# Sheet1-backup.net
KiCad netlist of a schematic drawn in Altium Designer
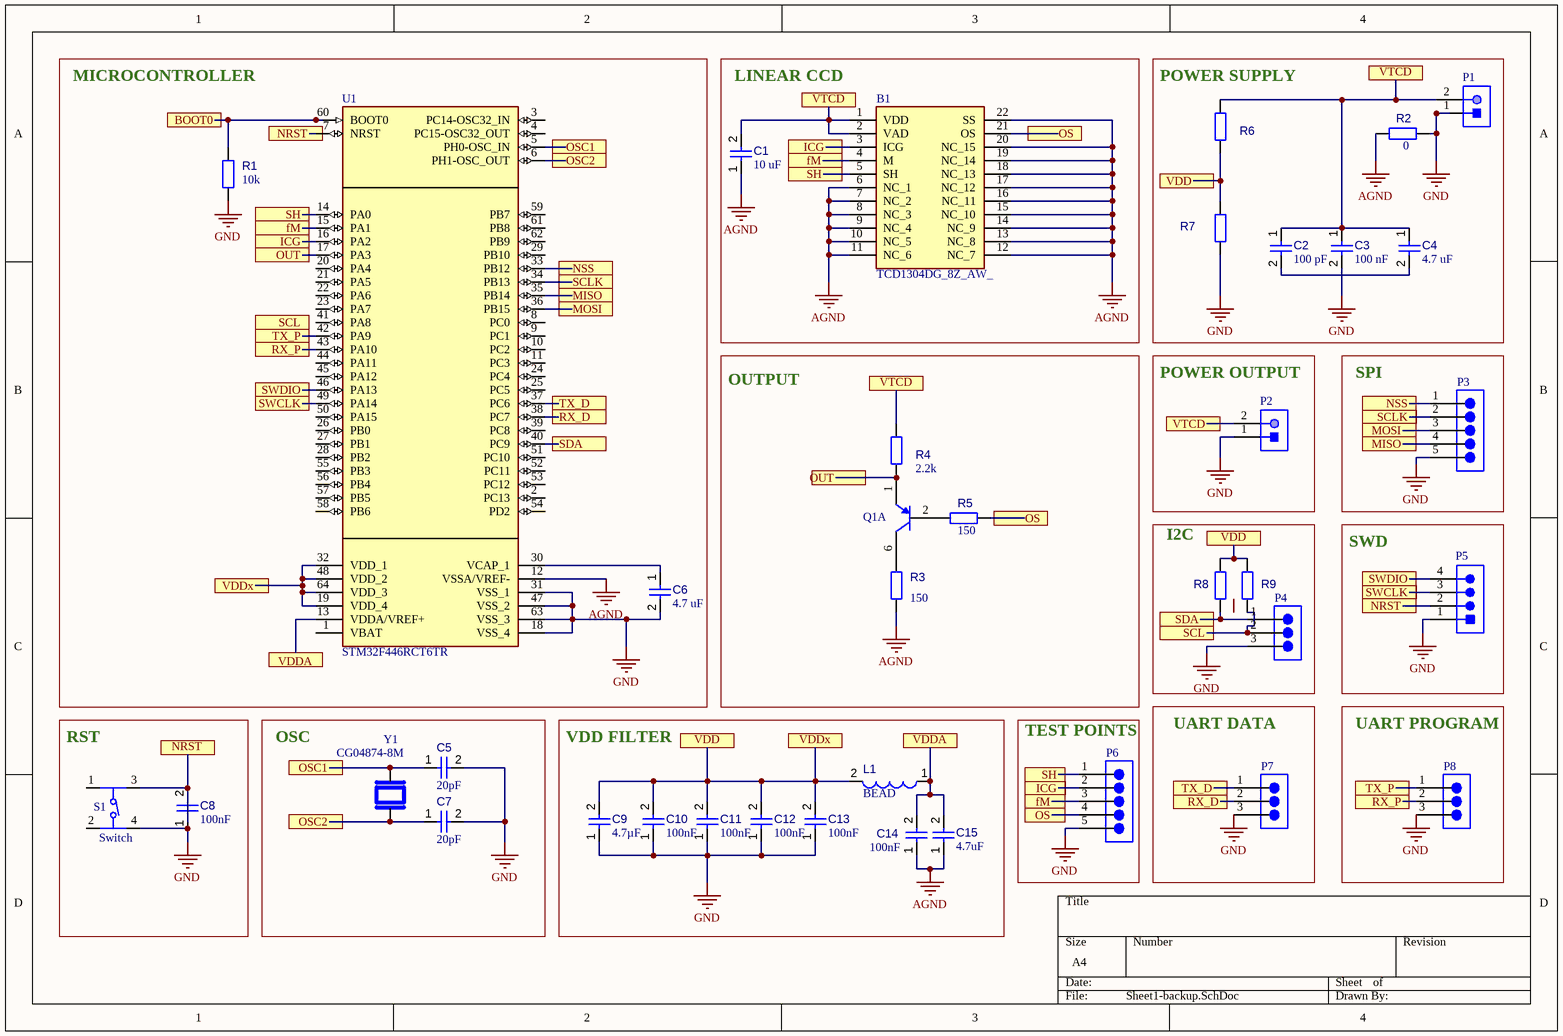
[diagram p0: Sheet1-backup.SchDoc]

(export (version "E")
  (design (tool "Eeschema 10.0.6"))
  (components
    (comp (ref "B1")
      (value "TCD1304DG_8Z_AW_")
      (footprint "DIP1016W62P254L4160H372Q22N")
      (description "Image Sensors & Color Sensors CCD Linear Sensor 3648 8x20 54mm")
      (fields
        (field (name "MOUSER PART NUMBER") "757-TCD1304DG8ZAW")
        (field (name "MANUFACTURER_PART_NUMBER") "TCD1304DG(8Z,AW)")
      )
      (libsource (lib "Sensors") (part "TCD1304DG_8Z_AW_"))
    )
    (comp (ref "C1")
      (value "10 uF")
      (footprint "CAPC1005X56X25LL10T15")
      (description "Chip Capacitor, 0.1 uF, +/- 5%, 16 V, 0402 (1005 Metric)")
      (fields (field (name "TOLERANCE") "5%") (field (name "Comment") "Capacitor 0.1 uF +/- 5% 16 V 0402"))
      (libsource (lib "Francisco Spaltro") (part "CAP-NP-2"))
    )
    (comp (ref "C2")
      (value "100 pF")
      (footprint "CAPC2013X95X50LL10T25")
      (description "Chip Capacitor, 100 nF, +/- 10%, 50 V, 0805 (2012 Metric)")
      (fields (field (name "TOLERANCE") "10%") (field (name "Comment") "Capacitor 100 nF +/-10% 50 V 0805"))
      (libsource (lib "Francisco Spaltro") (part "CAP-NP-2"))
    )
    (comp (ref "C3")
      (value "100 nF")
      (footprint "CAPC2013X95X50LL10T25")
      (description "Chip Capacitor, 100 nF, +/- 10%, 50 V, 0805 (2012 Metric)")
      (fields (field (name "TOLERANCE") "10%") (field (name "Comment") "Capacitor 100 nF +/-10% 50 V 0805"))
      (libsource (lib "Francisco Spaltro") (part "CAP-NP-2"))
    )
    (comp (ref "C4")
      (value "4.7 uF")
      (footprint "CAPC2013X95X50LL10T25")
      (description "Chip Capacitor, 100 nF, +/- 10%, 50 V, 0805 (2012 Metric)")
      (fields (field (name "TOLERANCE") "10%") (field (name "Comment") "Capacitor 100 nF +/-10% 50 V 0805"))
      (libsource (lib "Francisco Spaltro") (part "CAP-NP-2"))
    )
    (comp (ref "C5")
      (value "20pF")
      (footprint "CAPC1005X56X25ML10T15")
      (description "Chip Capacitor, 0.5 pF, +/- 0.1pF, 25 V, 0402 (1005 Metric)")
      (fields
        (field (name "TOLERANCE") "20%")
        (field (name "Comment") "Capacitor 0.5 pF +/- 0.1pF 25 V 0402")
      )
      (libsource (lib "Francisco Spaltro") (part "CAP-NP-2"))
    )
    (comp (ref "C6")
      (value "4.7 uF")
      (footprint "CAPC2013X95X50LL10T25")
      (description "Chip Capacitor, 100 nF, +/- 10%, 50 V, 0805 (2012 Metric)")
      (fields (field (name "TOLERANCE") "10%") (field (name "Comment") "Capacitor 100 nF +/-10% 50 V 0805"))
      (libsource (lib "Francisco Spaltro") (part "CAP-NP-2"))
    )
    (comp (ref "C7")
      (value "20pF")
      (footprint "CAPC1005X56X25ML10T15")
      (description "Chip Capacitor, 0.5 pF, +/- 0.1pF, 25 V, 0402 (1005 Metric)")
      (fields
        (field (name "TOLERANCE") "20%")
        (field (name "Comment") "Capacitor 0.5 pF +/- 0.1pF 25 V 0402")
      )
      (libsource (lib "Francisco Spaltro") (part "CAP-NP-2"))
    )
    (comp (ref "C8")
      (value "100nF")
      (footprint "CAPC1005X56X25LL10T15")
      (description "Chip Capacitor, 0.1 uF, +/- 5%, 16 V, 0402 (1005 Metric)")
      (fields (field (name "TOLERANCE") "5%") (field (name "Comment") "Capacitor 0.1 uF +/- 5% 16 V 0402"))
      (libsource (lib "Francisco Spaltro") (part "CAP-NP-2"))
    )
    (comp (ref "C9")
      (value "4.7µF")
      (footprint "CAPC0603(1608)100_L")
      (description "Chip Capacitor, 4.7µF +/-20%, 10V, 0603, Thickness 1 mm")
      (fields (field (name "TOLERANCE") "10%") (field (name "Comment") "Capacitor 4.7µF +/-20% 10V 0603"))
      (libsource (lib "Francisco Spaltro") (part "CAP-NP-2"))
    )
    (comp (ref "C10")
      (value "100nF")
      (footprint "CAPC2013X95X50LL10T25")
      (description "Chip Capacitor, 100 nF, +/- 10%, 50 V, 0805 (2012 Metric)")
      (fields (field (name "TOLERANCE") "10%") (field (name "Comment") "Capacitor 100 nF +/-10% 50 V 0805"))
      (libsource (lib "Francisco Spaltro") (part "CAP-NP-2"))
    )
    (comp (ref "C11")
      (value "100nF")
      (footprint "CAPC2013X95X50LL10T25")
      (description "Chip Capacitor, 100 nF, +/- 10%, 50 V, 0805 (2012 Metric)")
      (fields (field (name "TOLERANCE") "10%") (field (name "Comment") "Capacitor 100 nF +/-10% 50 V 0805"))
      (libsource (lib "Francisco Spaltro") (part "CAP-NP-2"))
    )
    (comp (ref "C12")
      (value "100nF")
      (footprint "CAPC2013X95X50LL10T25")
      (description "Chip Capacitor, 100 nF, +/- 10%, 50 V, 0805 (2012 Metric)")
      (fields (field (name "TOLERANCE") "10%") (field (name "Comment") "Capacitor 100 nF +/-10% 50 V 0805"))
      (libsource (lib "Francisco Spaltro") (part "CAP-NP-2"))
    )
    (comp (ref "C13")
      (value "100nF")
      (footprint "CAPC2013X95X50LL10T25")
      (description "Chip Capacitor, 100 nF, +/- 10%, 50 V, 0805 (2012 Metric)")
      (fields (field (name "TOLERANCE") "10%") (field (name "Comment") "Capacitor 100 nF +/-10% 50 V 0805"))
      (libsource (lib "Francisco Spaltro") (part "CAP-NP-2"))
    )
    (comp (ref "C14")
      (value "100nF")
      (footprint "CAPC2013X95X50LL10T25")
      (description "Chip Capacitor, 100 nF, +/- 10%, 50 V, 0805 (2012 Metric)")
      (fields (field (name "TOLERANCE") "10%") (field (name "Comment") "Capacitor 100 nF +/-10% 50 V 0805"))
      (libsource (lib "Francisco Spaltro") (part "CAP-NP-2"))
    )
    (comp (ref "C15")
      (value "4.7uF")
      (footprint "CAPC2013X95X50LL10T25")
      (description "Chip Capacitor, 100 nF, +/- 10%, 50 V, 0805 (2012 Metric)")
      (fields (field (name "TOLERANCE") "10%") (field (name "Comment") "Capacitor 100 nF +/-10% 50 V 0805"))
      (libsource (lib "Francisco Spaltro") (part "CAP-NP-2"))
    )
    (comp (ref "L1")
      (value "BEAD")
      (footprint "WE-LQS 4018")
      (description "WE-LQS SMD Power Inductor, L=33 µH")
      (fields (field (name "TOLERANCE") "20%") (field (name "Comment") "74404042330"))
      (libsource (lib "Francisco Spaltro") (part "CMP-001-0020-1"))
    )
    (comp (ref "P1")
      (value "~")
      (footprint "JST-S2B-PH-K-S_V")
      (fields (field (name "MANUFACTURER") "Japan Solderless Terminals"))
      (libsource (lib "Francisco Spaltro") (part "CN-1P-M-R2"))
    )
    (comp (ref "P2")
      (value "~")
      (footprint "JST-S2B-PH-K-S_V")
      (fields (field (name "MANUFACTURER") "Japan Solderless Terminals"))
      (libsource (lib "Francisco Spaltro") (part "CN-1P-M-R2"))
    )
    (comp (ref "P3")
      (value "~")
      (footprint "PCB_5POS_PIN")
      (libsource (lib "Componentes") (part "5-POS-PIN"))
    )
    (comp (ref "P4")
      (value "~")
      (footprint "PCB_3POS_PIN")
      (libsource (lib "Componentes") (part "3-POS-PIN"))
    )
    (comp (ref "P5")
      (value "~")
      (footprint "JST-S4B-XH-A(LF)(SN)_V")
      (fields (field (name "MANUFACTURER") "JST"))
      (libsource (lib "Francisco Spaltro") (part "CN-1P-M-R4"))
    )
    (comp (ref "P6")
      (value "~")
      (footprint "PCB_5POS_PIN")
      (libsource (lib "Componentes") (part "5-POS-PIN"))
    )
    (comp (ref "P7")
      (value "~")
      (footprint "PCB_3POS_PIN")
      (libsource (lib "Componentes") (part "3-POS-PIN"))
    )
    (comp (ref "P8")
      (value "~")
      (footprint "PCB_3POS_PIN")
      (libsource (lib "Componentes") (part "3-POS-PIN"))
    )
    (comp (ref "Q1")
      (value "~")
      (footprint "NXP-SOT457-6_V")
      (description "PNP/PNP Matched Double Transistors, 175 MHz, -65 to 150 degC, 6-Pin SOT457, RoHS, Tape and Reel")
      (fields (field (name "MANUFACTURER") "NXP") (field (name "POWER") "380mW"))
      (libsource (lib "Francisco Spaltro") (part "BJT-PNP-EBC-EBC-6"))
    )
    (comp (ref "R1")
      (value "10k")
      (footprint "RESC0402(1005)_L")
      (description "10K 0.063W 1% 0402 (1005 Metric)  SMD")
      (fields (field (name "POWER") "63mW") (field (name "TOLERANCE") "1%"))
      (libsource (lib "") (part "10KR2F_1"))
    )
    (comp (ref "R2")
      (value "0")
      (footprint "RESC0402(1005)_L")
      (description "10K 0.063W 1% 0402 (1005 Metric)  SMD")
      (fields (field (name "POWER") "63mW") (field (name "TOLERANCE") "1%"))
      (libsource (lib "Francisco Spaltro") (part "10KR2F"))
    )
    (comp (ref "R3")
      (value "150")
      (footprint "RESC0402(1005)_L")
      (description "10K 0.063W 1% 0402 (1005 Metric)  SMD")
      (fields (field (name "POWER") "63mW") (field (name "TOLERANCE") "1%"))
      (libsource (lib "") (part "10KR2F_2"))
    )
    (comp (ref "R4")
      (value "2.2k")
      (footprint "RESC0402(1005)_L")
      (description "10K 0.063W 1% 0402 (1005 Metric)  SMD")
      (fields (field (name "POWER") "63mW") (field (name "TOLERANCE") "1%"))
      (libsource (lib "") (part "10KR2F_2"))
    )
    (comp (ref "R5")
      (value "150")
      (footprint "RESC0402(1005)_L")
      (description "10K 0.063W 1% 0402 (1005 Metric)  SMD")
      (fields (field (name "POWER") "63mW") (field (name "TOLERANCE") "1%"))
      (libsource (lib "Francisco Spaltro") (part "10KR2F"))
    )
    (comp (ref "R6")
      (value "10KR2F")
      (footprint "RESC0402(1005)_L")
      (description "10K 0.063W 1% 0402 (1005 Metric)  SMD")
      (fields (field (name "POWER") "63mW") (field (name "TOLERANCE") "1%"))
      (libsource (lib "") (part "10KR2F_2"))
    )
    (comp (ref "R7")
      (value "10KR2F")
      (footprint "RESC0402(1005)_L")
      (description "10K 0.063W 1% 0402 (1005 Metric)  SMD")
      (fields (field (name "POWER") "63mW") (field (name "TOLERANCE") "1%"))
      (libsource (lib "") (part "10KR2F_2"))
    )
    (comp (ref "R8")
      (value "10KR2F")
      (footprint "RESC0402(1005)_L")
      (description "10K 0.063W 1% 0402 (1005 Metric)  SMD")
      (fields (field (name "POWER") "63mW") (field (name "TOLERANCE") "1%"))
      (libsource (lib "") (part "10KR2F_2"))
    )
    (comp (ref "R9")
      (value "10KR2F")
      (footprint "RESC0402(1005)_L")
      (description "10K 0.063W 1% 0402 (1005 Metric)  SMD")
      (fields (field (name "POWER") "63mW") (field (name "TOLERANCE") "1%"))
      (libsource (lib "") (part "10KR2F_2"))
    )
    (comp (ref "S1")
      (value "Switch")
      (footprint "430152070826")
      (description "Tactile Switch SPST-NO Top Actuated Surface Mount")
      (fields (field (name "MF") "WÃ¼rth Elektronik") (field (name "MP") "430152070826"))
      (libsource (lib "Componentes") (part "Switch"))
    )
    (comp (ref "U1")
      (value "STM32F446RCT6TR")
      (footprint "QFP50P1200X1200X160-64N")
      (fields (field (name "MF") "STMicroelectronics"))
      (libsource (lib "IC") (part "STM32F446RCT6TR"))
    )
    (comp (ref "Y1")
      (value "CG04874-8M")
      (footprint "XTALDFN320X250X100-2N")
      (description "8 MHz ±20ppm Crystal 8pF 500 Ohms 2-SMD, No Lead")
      (fields (field (name "MF") "NDK America, Inc."))
      (libsource (lib "Componentes") (part "CG04874-8M"))
    )
  )
  (nets
    (net (code "1") (name "/BOOT0") (class "Default")
      (node (ref "R1") (pin "2") (pinfunction "2_2") (pintype "passive"))
      (node (ref "U1") (pin "60") (pinfunction "BOOT0_60") (pintype "input"))
    )
    (net (code "2") (name "/ICG") (class "Default")
      (node (ref "B1") (pin "3") (pinfunction "ICG_3") (pintype "passive"))
      (node (ref "P6") (pin "2") (pinfunction "2_2") (pintype "passive"))
      (node (ref "U1") (pin "16") (pinfunction "PA2_16") (pintype "bidirectional"))
    )
    (net (code "3") (name "/MISO") (class "Default")
      (node (ref "P3") (pin "4") (pinfunction "4_4") (pintype "passive"))
      (node (ref "U1") (pin "35") (pinfunction "PB14_35") (pintype "bidirectional"))
    )
    (net (code "4") (name "/MOSI") (class "Default")
      (node (ref "P3") (pin "3") (pinfunction "3_3") (pintype "passive"))
      (node (ref "U1") (pin "36") (pinfunction "PB15_36") (pintype "bidirectional"))
    )
    (net (code "5") (name "/NRST") (class "Default")
      (node (ref "C8") (pin "2") (pinfunction "2_2") (pintype "passive"))
      (node (ref "P5") (pin "2") (pinfunction "2_2") (pintype "passive"))
      (node (ref "S1") (pin "3") (pinfunction "3_3") (pintype "passive"))
      (node (ref "U1") (pin "7") (pinfunction "NRST_7") (pintype "bidirectional"))
    )
    (net (code "6") (name "/NSS") (class "Default")
      (node (ref "P3") (pin "1") (pinfunction "1_1") (pintype "passive"))
      (node (ref "U1") (pin "33") (pinfunction "PB12_33") (pintype "bidirectional"))
    )
    (net (code "7") (name "/OS") (class "Default")
      (node (ref "B1") (pin "21") (pinfunction "OS_21") (pintype "passive"))
      (node (ref "P6") (pin "4") (pinfunction "4_4") (pintype "passive"))
      (node (ref "R5") (pin "1") (pinfunction "1_1") (pintype "passive"))
    )
    (net (code "8") (name "/OSC1") (class "Default")
      (node (ref "C5") (pin "1") (pinfunction "1_1") (pintype "passive"))
      (node (ref "U1") (pin "5") (pinfunction "PH0-OSC_IN_5") (pintype "bidirectional"))
      (node (ref "Y1") (pin "2") (pinfunction "2_2") (pintype "passive"))
    )
    (net (code "9") (name "/OSC2") (class "Default")
      (node (ref "C7") (pin "1") (pinfunction "1_1") (pintype "passive"))
      (node (ref "U1") (pin "6") (pinfunction "PH1-OSC_OUT_6") (pintype "bidirectional"))
      (node (ref "Y1") (pin "1") (pinfunction "1_1") (pintype "passive"))
    )
    (net (code "10") (name "/OUT") (class "Default")
      (node (ref "Q1") (pin "1") (pinfunction "E1_1") (pintype "passive"))
      (node (ref "R4") (pin "2") (pinfunction "2_2") (pintype "passive"))
      (node (ref "U1") (pin "17") (pinfunction "PA3_17") (pintype "bidirectional"))
    )
    (net (code "11") (name "/RX_D") (class "Default")
      (node (ref "P7") (pin "2") (pinfunction "2_2") (pintype "passive"))
      (node (ref "U1") (pin "38") (pinfunction "PC7_38") (pintype "bidirectional"))
    )
    (net (code "12") (name "/RX_P") (class "Default")
      (node (ref "P8") (pin "2") (pinfunction "2_2") (pintype "passive"))
      (node (ref "U1") (pin "43") (pinfunction "PA10_43") (pintype "bidirectional"))
    )
    (net (code "13") (name "/SCL") (class "Default")
      (node (ref "P4") (pin "2") (pinfunction "2_2") (pintype "passive"))
      (node (ref "R9") (pin "2") (pinfunction "2_2") (pintype "passive"))
    )
    (net (code "14") (name "/SCLK") (class "Default")
      (node (ref "P3") (pin "2") (pinfunction "2_2") (pintype "passive"))
      (node (ref "U1") (pin "34") (pinfunction "PB13_34") (pintype "bidirectional"))
    )
    (net (code "15") (name "/SDA") (class "Default")
      (node (ref "P4") (pin "1") (pinfunction "1_1") (pintype "passive"))
      (node (ref "R8") (pin "2") (pinfunction "2_2") (pintype "passive"))
      (node (ref "U1") (pin "40") (pinfunction "PC9_40") (pintype "bidirectional"))
    )
    (net (code "16") (name "/SH") (class "Default")
      (node (ref "B1") (pin "5") (pinfunction "SH_5") (pintype "passive"))
      (node (ref "P6") (pin "1") (pinfunction "1_1") (pintype "passive"))
      (node (ref "U1") (pin "14") (pinfunction "PA0_14") (pintype "bidirectional"))
    )
    (net (code "17") (name "/SWCLK") (class "Default")
      (node (ref "P5") (pin "3") (pinfunction "3_3") (pintype "passive"))
      (node (ref "U1") (pin "49") (pinfunction "PA14_49") (pintype "bidirectional"))
    )
    (net (code "18") (name "/SWDIO") (class "Default")
      (node (ref "P5") (pin "4") (pinfunction "4_4") (pintype "passive"))
      (node (ref "U1") (pin "46") (pinfunction "PA13_46") (pintype "bidirectional"))
    )
    (net (code "19") (name "/TX_D") (class "Default")
      (node (ref "P7") (pin "1") (pinfunction "1_1") (pintype "passive"))
      (node (ref "U1") (pin "37") (pinfunction "PC6_37") (pintype "bidirectional"))
    )
    (net (code "20") (name "/TX_P") (class "Default")
      (node (ref "P8") (pin "1") (pinfunction "1_1") (pintype "passive"))
      (node (ref "U1") (pin "42") (pinfunction "PA9_42") (pintype "bidirectional"))
    )
    (net (code "21") (name "/VDD") (class "Default")
      (node (ref "C10") (pin "2") (pinfunction "2_2") (pintype "passive"))
      (node (ref "C11") (pin "2") (pinfunction "2_2") (pintype "passive"))
      (node (ref "C12") (pin "2") (pinfunction "2_2") (pintype "passive"))
      (node (ref "C13") (pin "2") (pinfunction "2_2") (pintype "passive"))
      (node (ref "C9") (pin "2") (pinfunction "2_2") (pintype "passive"))
      (node (ref "L1") (pin "2") (pinfunction "2_2") (pintype "passive"))
      (node (ref "R6") (pin "2") (pinfunction "2_2") (pintype "passive"))
      (node (ref "R7") (pin "1") (pinfunction "1_1") (pintype "passive"))
      (node (ref "R8") (pin "1") (pinfunction "1_1") (pintype "passive"))
      (node (ref "R9") (pin "1") (pinfunction "1_1") (pintype "passive"))
      (node (ref "U1") (pin "19") (pinfunction "VDD_4_19") (pintype "power_in"))
      (node (ref "U1") (pin "32") (pinfunction "VDD_1_32") (pintype "power_in"))
      (node (ref "U1") (pin "48") (pinfunction "VDD_2_48") (pintype "power_in"))
      (node (ref "U1") (pin "64") (pinfunction "VDD_3_64") (pintype "power_in"))
    )
    (net (code "22") (name "/VDDA") (class "Default")
      (node (ref "C14") (pin "2") (pinfunction "2_2") (pintype "passive"))
      (node (ref "C15") (pin "2") (pinfunction "2_2") (pintype "passive"))
      (node (ref "L1") (pin "1") (pinfunction "1_1") (pintype "passive"))
      (node (ref "U1") (pin "13") (pinfunction "VDDA/VREF+_13") (pintype "power_in"))
    )
    (net (code "23") (name "/VTCD") (class "Default")
      (node (ref "B1") (pin "1") (pinfunction "VDD_1") (pintype "power_in"))
      (node (ref "B1") (pin "2") (pinfunction "VAD_2") (pintype "power_in"))
      (node (ref "C1") (pin "2") (pinfunction "2_2") (pintype "passive"))
      (node (ref "C2") (pin "1") (pinfunction "1_1") (pintype "passive"))
      (node (ref "C3") (pin "1") (pinfunction "1_1") (pintype "passive"))
      (node (ref "C4") (pin "1") (pinfunction "1_1") (pintype "passive"))
      (node (ref "P1") (pin "2") (pinfunction "2_2") (pintype "passive"))
      (node (ref "P2") (pin "2") (pinfunction "2_2") (pintype "passive"))
      (node (ref "R4") (pin "1") (pinfunction "1_1") (pintype "passive"))
      (node (ref "R6") (pin "1") (pinfunction "1_1") (pintype "passive"))
    )
    (net (code "24") (name "/fM") (class "Default")
      (node (ref "B1") (pin "4") (pinfunction "M_4") (pintype "passive"))
      (node (ref "P6") (pin "3") (pinfunction "3_3") (pintype "passive"))
      (node (ref "U1") (pin "15") (pinfunction "PA1_15") (pintype "bidirectional"))
    )
    (net (code "25") (name "AGND") (class "Default")
      (node (ref "B1") (pin "10") (pinfunction "NC_5_10") (pintype "passive"))
      (node (ref "B1") (pin "11") (pinfunction "NC_6_11") (pintype "passive"))
      (node (ref "B1") (pin "12") (pinfunction "NC_7_12") (pintype "passive"))
      (node (ref "B1") (pin "13") (pinfunction "NC_8_13") (pintype "passive"))
      (node (ref "B1") (pin "14") (pinfunction "NC_9_14") (pintype "passive"))
      (node (ref "B1") (pin "15") (pinfunction "NC_10_15") (pintype "passive"))
      (node (ref "B1") (pin "16") (pinfunction "NC_11_16") (pintype "passive"))
      (node (ref "B1") (pin "17") (pinfunction "NC_12_17") (pintype "passive"))
      (node (ref "B1") (pin "18") (pinfunction "NC_13_18") (pintype "passive"))
      (node (ref "B1") (pin "19") (pinfunction "NC_14_19") (pintype "passive"))
      (node (ref "B1") (pin "20") (pinfunction "NC_15_20") (pintype "passive"))
      (node (ref "B1") (pin "22") (pinfunction "SS_22") (pintype "passive"))
      (node (ref "B1") (pin "6") (pinfunction "NC_1_6") (pintype "passive"))
      (node (ref "B1") (pin "7") (pinfunction "NC_2_7") (pintype "passive"))
      (node (ref "B1") (pin "8") (pinfunction "NC_3_8") (pintype "passive"))
      (node (ref "B1") (pin "9") (pinfunction "NC_4_9") (pintype "passive"))
      (node (ref "C1") (pin "1") (pinfunction "1_1") (pintype "passive"))
      (node (ref "C14") (pin "1") (pinfunction "1_1") (pintype "passive"))
      (node (ref "C15") (pin "1") (pinfunction "1_1") (pintype "passive"))
      (node (ref "R2") (pin "2") (pinfunction "2_2") (pintype "passive"))
      (node (ref "R3") (pin "2") (pinfunction "2_2") (pintype "passive"))
      (node (ref "U1") (pin "12") (pinfunction "VSSA/VREF-_12") (pintype "power_in"))
    )
    (net (code "26") (name "GND") (class "Default")
      (node (ref "C10") (pin "1") (pinfunction "1_1") (pintype "passive"))
      (node (ref "C11") (pin "1") (pinfunction "1_1") (pintype "passive"))
      (node (ref "C12") (pin "1") (pinfunction "1_1") (pintype "passive"))
      (node (ref "C13") (pin "1") (pinfunction "1_1") (pintype "passive"))
      (node (ref "C3") (pin "2") (pinfunction "2_2") (pintype "passive"))
      (node (ref "C5") (pin "2") (pinfunction "2_2") (pintype "passive"))
      (node (ref "C6") (pin "2") (pinfunction "2_2") (pintype "passive"))
      (node (ref "C7") (pin "2") (pinfunction "2_2") (pintype "passive"))
      (node (ref "C8") (pin "1") (pinfunction "1_1") (pintype "passive"))
      (node (ref "C9") (pin "1") (pinfunction "1_1") (pintype "passive"))
      (node (ref "P1") (pin "1") (pinfunction "1_1") (pintype "passive"))
      (node (ref "P2") (pin "1") (pinfunction "1_1") (pintype "passive"))
      (node (ref "P3") (pin "5") (pinfunction "5_5") (pintype "passive"))
      (node (ref "P4") (pin "3") (pinfunction "3_3") (pintype "passive"))
      (node (ref "P5") (pin "1") (pinfunction "1_1") (pintype "passive"))
      (node (ref "P6") (pin "5") (pinfunction "5_5") (pintype "passive"))
      (node (ref "P7") (pin "3") (pinfunction "3_3") (pintype "passive"))
      (node (ref "P8") (pin "3") (pinfunction "3_3") (pintype "passive"))
      (node (ref "R1") (pin "1") (pinfunction "1_1") (pintype "passive"))
      (node (ref "R2") (pin "1") (pinfunction "1_1") (pintype "passive"))
      (node (ref "R7") (pin "2") (pinfunction "2_2") (pintype "passive"))
      (node (ref "S1") (pin "4") (pinfunction "4_4") (pintype "passive"))
      (node (ref "U1") (pin "18") (pinfunction "VSS_4_18") (pintype "power_in"))
      (node (ref "U1") (pin "31") (pinfunction "VSS_1_31") (pintype "power_in"))
      (node (ref "U1") (pin "47") (pinfunction "VSS_2_47") (pintype "power_in"))
      (node (ref "U1") (pin "63") (pinfunction "VSS_3_63") (pintype "power_in"))
    )
    (net (code "27") (name "Net-(C2-Pad2)") (class "Default")
      (node (ref "C2") (pin "2") (pinfunction "2_2") (pintype "passive"))
      (node (ref "C4") (pin "2") (pinfunction "2_2") (pintype "passive"))
    )
    (net (code "28") (name "Net-(Q1A-B1)") (class "Default")
      (node (ref "Q1") (pin "2") (pinfunction "B1_2") (pintype "passive"))
      (node (ref "R5") (pin "2") (pinfunction "2_2") (pintype "passive"))
    )
    (net (code "29") (name "Net-(Q1A-C1)") (class "Default")
      (node (ref "Q1") (pin "6") (pinfunction "C1_6") (pintype "passive"))
      (node (ref "R3") (pin "1") (pinfunction "1_1") (pintype "passive"))
    )
    (net (code "30") (name "Net-(U1-VCAP_1)") (class "Default")
      (node (ref "C6") (pin "1") (pinfunction "1_1") (pintype "passive"))
      (node (ref "U1") (pin "30") (pinfunction "VCAP_1_30") (pintype "power_in"))
    )
    (net (code "31") (name "unconnected-(S1-Pad1)") (class "Default")
      (node (ref "S1") (pin "1") (pinfunction "1_1") (pintype "passive"))
    )
    (net (code "32") (name "unconnected-(S1-Pad2)") (class "Default")
      (node (ref "S1") (pin "2") (pinfunction "2_2") (pintype "passive"))
    )
    (net (code "33") (name "unconnected-(U1-PA4-Pad20)") (class "Default")
      (node (ref "U1") (pin "20") (pinfunction "PA4_20") (pintype "bidirectional"))
    )
    (net (code "34") (name "unconnected-(U1-PA5-Pad21)") (class "Default")
      (node (ref "U1") (pin "21") (pinfunction "PA5_21") (pintype "bidirectional"))
    )
    (net (code "35") (name "unconnected-(U1-PA6-Pad22)") (class "Default")
      (node (ref "U1") (pin "22") (pinfunction "PA6_22") (pintype "bidirectional"))
    )
    (net (code "36") (name "unconnected-(U1-PA7-Pad23)") (class "Default")
      (node (ref "U1") (pin "23") (pinfunction "PA7_23") (pintype "bidirectional"))
    )
    (net (code "37") (name "unconnected-(U1-PA8-Pad41)") (class "Default")
      (node (ref "U1") (pin "41") (pinfunction "PA8_41") (pintype "bidirectional"))
    )
    (net (code "38") (name "unconnected-(U1-PA11-Pad44)") (class "Default")
      (node (ref "U1") (pin "44") (pinfunction "PA11_44") (pintype "bidirectional"))
    )
    (net (code "39") (name "unconnected-(U1-PA12-Pad45)") (class "Default")
      (node (ref "U1") (pin "45") (pinfunction "PA12_45") (pintype "bidirectional"))
    )
    (net (code "40") (name "unconnected-(U1-PA15-Pad50)") (class "Default")
      (node (ref "U1") (pin "50") (pinfunction "PA15_50") (pintype "bidirectional"))
    )
    (net (code "41") (name "unconnected-(U1-PB0-Pad26)") (class "Default")
      (node (ref "U1") (pin "26") (pinfunction "PB0_26") (pintype "bidirectional"))
    )
    (net (code "42") (name "unconnected-(U1-PB1-Pad27)") (class "Default")
      (node (ref "U1") (pin "27") (pinfunction "PB1_27") (pintype "bidirectional"))
    )
    (net (code "43") (name "unconnected-(U1-PB2-Pad28)") (class "Default")
      (node (ref "U1") (pin "28") (pinfunction "PB2_28") (pintype "bidirectional"))
    )
    (net (code "44") (name "unconnected-(U1-PB3-Pad55)") (class "Default")
      (node (ref "U1") (pin "55") (pinfunction "PB3_55") (pintype "bidirectional"))
    )
    (net (code "45") (name "unconnected-(U1-PB4-Pad56)") (class "Default")
      (node (ref "U1") (pin "56") (pinfunction "PB4_56") (pintype "bidirectional"))
    )
    (net (code "46") (name "unconnected-(U1-PB5-Pad57)") (class "Default")
      (node (ref "U1") (pin "57") (pinfunction "PB5_57") (pintype "bidirectional"))
    )
    (net (code "47") (name "unconnected-(U1-PB6-Pad58)") (class "Default")
      (node (ref "U1") (pin "58") (pinfunction "PB6_58") (pintype "bidirectional"))
    )
    (net (code "48") (name "unconnected-(U1-PB7-Pad59)") (class "Default")
      (node (ref "U1") (pin "59") (pinfunction "PB7_59") (pintype "bidirectional"))
    )
    (net (code "49") (name "unconnected-(U1-PB8-Pad61)") (class "Default")
      (node (ref "U1") (pin "61") (pinfunction "PB8_61") (pintype "bidirectional"))
    )
    (net (code "50") (name "unconnected-(U1-PB9-Pad62)") (class "Default")
      (node (ref "U1") (pin "62") (pinfunction "PB9_62") (pintype "bidirectional"))
    )
    (net (code "51") (name "unconnected-(U1-PB10-Pad29)") (class "Default")
      (node (ref "U1") (pin "29") (pinfunction "PB10_29") (pintype "bidirectional"))
    )
    (net (code "52") (name "unconnected-(U1-PC0-Pad8)") (class "Default")
      (node (ref "U1") (pin "8") (pinfunction "PC0_8") (pintype "bidirectional"))
    )
    (net (code "53") (name "unconnected-(U1-PC1-Pad9)") (class "Default")
      (node (ref "U1") (pin "9") (pinfunction "PC1_9") (pintype "bidirectional"))
    )
    (net (code "54") (name "unconnected-(U1-PC2-Pad10)") (class "Default")
      (node (ref "U1") (pin "10") (pinfunction "PC2_10") (pintype "bidirectional"))
    )
    (net (code "55") (name "unconnected-(U1-PC3-Pad11)") (class "Default")
      (node (ref "U1") (pin "11") (pinfunction "PC3_11") (pintype "bidirectional"))
    )
    (net (code "56") (name "unconnected-(U1-PC4-Pad24)") (class "Default")
      (node (ref "U1") (pin "24") (pinfunction "PC4_24") (pintype "bidirectional"))
    )
    (net (code "57") (name "unconnected-(U1-PC5-Pad25)") (class "Default")
      (node (ref "U1") (pin "25") (pinfunction "PC5_25") (pintype "bidirectional"))
    )
    (net (code "58") (name "unconnected-(U1-PC8-Pad39)") (class "Default")
      (node (ref "U1") (pin "39") (pinfunction "PC8_39") (pintype "bidirectional"))
    )
    (net (code "59") (name "unconnected-(U1-PC10-Pad51)") (class "Default")
      (node (ref "U1") (pin "51") (pinfunction "PC10_51") (pintype "bidirectional"))
    )
    (net (code "60") (name "unconnected-(U1-PC11-Pad52)") (class "Default")
      (node (ref "U1") (pin "52") (pinfunction "PC11_52") (pintype "bidirectional"))
    )
    (net (code "61") (name "unconnected-(U1-PC12-Pad53)") (class "Default")
      (node (ref "U1") (pin "53") (pinfunction "PC12_53") (pintype "bidirectional"))
    )
    (net (code "62") (name "unconnected-(U1-PC13-Pad2)") (class "Default")
      (node (ref "U1") (pin "2") (pinfunction "PC13_2") (pintype "bidirectional"))
    )
    (net (code "63") (name "unconnected-(U1-PC14-OSC32_IN-Pad3)") (class "Default")
      (node (ref "U1") (pin "3") (pinfunction "PC14-OSC32_IN_3") (pintype "bidirectional"))
    )
    (net (code "64") (name "unconnected-(U1-PC15-OSC32_OUT-Pad4)") (class "Default")
      (node (ref "U1") (pin "4") (pinfunction "PC15-OSC32_OUT_4") (pintype "bidirectional"))
    )
    (net (code "65") (name "unconnected-(U1-PD2-Pad54)") (class "Default")
      (node (ref "U1") (pin "54") (pinfunction "PD2_54") (pintype "bidirectional"))
    )
    (net (code "66") (name "unconnected-(U1-VBAT-Pad1)") (class "Default")
      (node (ref "U1") (pin "1") (pinfunction "VBAT_1") (pintype "power_in"))
    )
  )
)
